# sampling.net
KiCad netlist of a schematic drawn in EAGLE
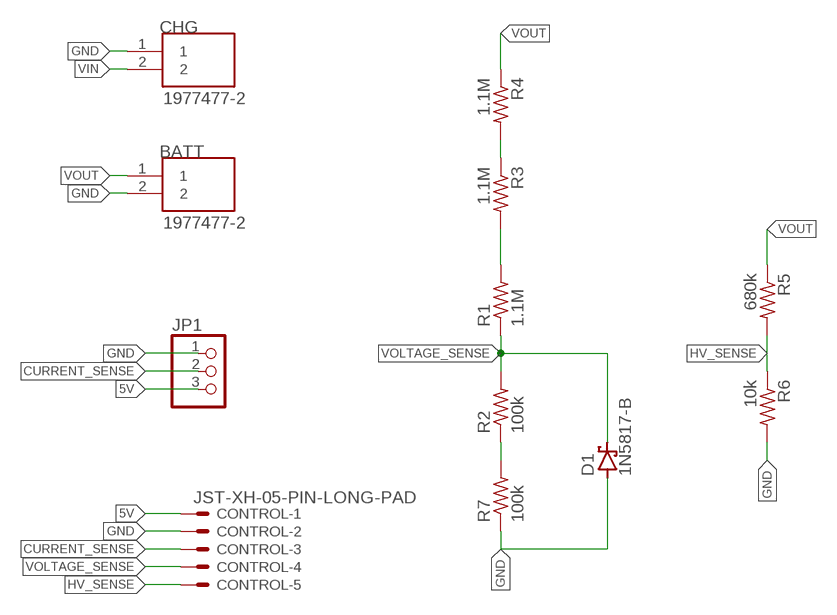
[diagram p0: schematic, sheet 1]

(export (version "E")
  (design (tool "Eeschema 10.0.6"))
  (components
    (comp (ref "BATT")
      (value "1977477-2")
      (footprint "eagle-import:TE_1977477-2")
      (fields (field (name "MF") "TE Connectivity"))
      (libsource (lib "eagle-import") (part "1977477-2"))
    )
    (comp (ref "CHG")
      (value "1977477-2")
      (footprint "eagle-import:TE_1977477-2")
      (fields (field (name "MF") "TE Connectivity"))
      (libsource (lib "eagle-import") (part "1977477-2"))
    )
    (comp (ref "CONTROL")
      (value "JST-XH-05-PIN-LONG-PAD")
      (footprint "eagle-import:JST-XH-05-PACKAGE-LONG-PAD")
      (libsource (lib "eagle-import") (part "JST-XH-05-PIN-LONG-PAD"))
    )
    (comp (ref "D1")
      (value "1N5817-B")
      (footprint "eagle-import:DO41-7.6")
      (libsource (lib "eagle-import") (part "1N5817-B"))
    )
    (comp (ref "JP1")
      (value "PINHD-1X3")
      (footprint "eagle-import:1X03")
      (libsource (lib "eagle-import") (part "PINHD-1X3"))
    )
    (comp (ref "R1")
      (value "1.1M")
      (footprint "eagle-import:R0805")
      (libsource (lib "eagle-import") (part "R-US_R0805"))
    )
    (comp (ref "R2")
      (value "100k")
      (footprint "eagle-import:R0805")
      (libsource (lib "eagle-import") (part "R-US_R0805"))
    )
    (comp (ref "R3")
      (value "1.1M")
      (footprint "eagle-import:R0805")
      (libsource (lib "eagle-import") (part "R-US_R0805"))
    )
    (comp (ref "R4")
      (value "1.1M")
      (footprint "eagle-import:R0805")
      (libsource (lib "eagle-import") (part "R-US_R0805"))
    )
    (comp (ref "R5")
      (value "680k")
      (footprint "eagle-import:0207_10")
      (libsource (lib "eagle-import") (part "R-US_0207/10"))
    )
    (comp (ref "R6")
      (value "10k")
      (footprint "eagle-import:0207_10")
      (libsource (lib "eagle-import") (part "R-US_0207/10"))
    )
    (comp (ref "R7")
      (value "100k")
      (footprint "eagle-import:R0805")
      (libsource (lib "eagle-import") (part "R-US_R0805"))
    )
  )
  (nets
    (net (code "1") (name "5V") (class "Default")
      (node (ref "CONTROL") (pin "1") (pinfunction "S_1") (pintype "passive"))
      (node (ref "JP1") (pin "3") (pinfunction "3_3") (pintype "passive"))
    )
    (net (code "2") (name "CURRENT_SENSE") (class "Default")
      (node (ref "CONTROL") (pin "3") (pinfunction "S_3") (pintype "passive"))
      (node (ref "JP1") (pin "2") (pinfunction "2_2") (pintype "passive"))
    )
    (net (code "3") (name "GND") (class "Default")
      (node (ref "BATT") (pin "2") (pinfunction "2_2") (pintype "passive"))
      (node (ref "CHG") (pin "1") (pinfunction "1_1") (pintype "passive"))
      (node (ref "CONTROL") (pin "2") (pinfunction "S_2") (pintype "passive"))
      (node (ref "D1") (pin "A") (pinfunction "A_A") (pintype "passive"))
      (node (ref "JP1") (pin "1") (pinfunction "1_1") (pintype "passive"))
      (node (ref "R6") (pin "2") (pinfunction "2_2") (pintype "passive"))
      (node (ref "R7") (pin "1") (pinfunction "1_1") (pintype "passive"))
    )
    (net (code "4") (name "HV_SENSE") (class "Default")
      (node (ref "CONTROL") (pin "5") (pinfunction "S_5") (pintype "passive"))
      (node (ref "R5") (pin "2") (pinfunction "2_2") (pintype "passive"))
      (node (ref "R6") (pin "1") (pinfunction "1_1") (pintype "passive"))
    )
    (net (code "5") (name "Net-(R1-Pad2)") (class "Default")
      (node (ref "R1") (pin "2") (pinfunction "2_2") (pintype "passive"))
      (node (ref "R3") (pin "2") (pinfunction "2_2") (pintype "passive"))
    )
    (net (code "6") (name "Net-(R2-Pad1)") (class "Default")
      (node (ref "R2") (pin "1") (pinfunction "1_1") (pintype "passive"))
      (node (ref "R7") (pin "2") (pinfunction "2_2") (pintype "passive"))
    )
    (net (code "7") (name "Net-(R3-Pad1)") (class "Default")
      (node (ref "R3") (pin "1") (pinfunction "1_1") (pintype "passive"))
      (node (ref "R4") (pin "2") (pinfunction "2_2") (pintype "passive"))
    )
    (net (code "8") (name "VIN") (class "Default")
      (node (ref "CHG") (pin "2") (pinfunction "2_2") (pintype "passive"))
    )
    (net (code "9") (name "VOLTAGE_SENSE") (class "Default")
      (node (ref "CONTROL") (pin "4") (pinfunction "S_4") (pintype "passive"))
      (node (ref "D1") (pin "C") (pinfunction "C_C") (pintype "passive"))
      (node (ref "R1") (pin "1") (pinfunction "1_1") (pintype "passive"))
      (node (ref "R2") (pin "2") (pinfunction "2_2") (pintype "passive"))
    )
    (net (code "10") (name "VOUT") (class "Default")
      (node (ref "BATT") (pin "1") (pinfunction "1_1") (pintype "passive"))
      (node (ref "R4") (pin "1") (pinfunction "1_1") (pintype "passive"))
      (node (ref "R5") (pin "1") (pinfunction "1_1") (pintype "passive"))
    )
  )
)
